# Water_motor_system.net
KiCad netlist of a schematic drawn in EAGLE
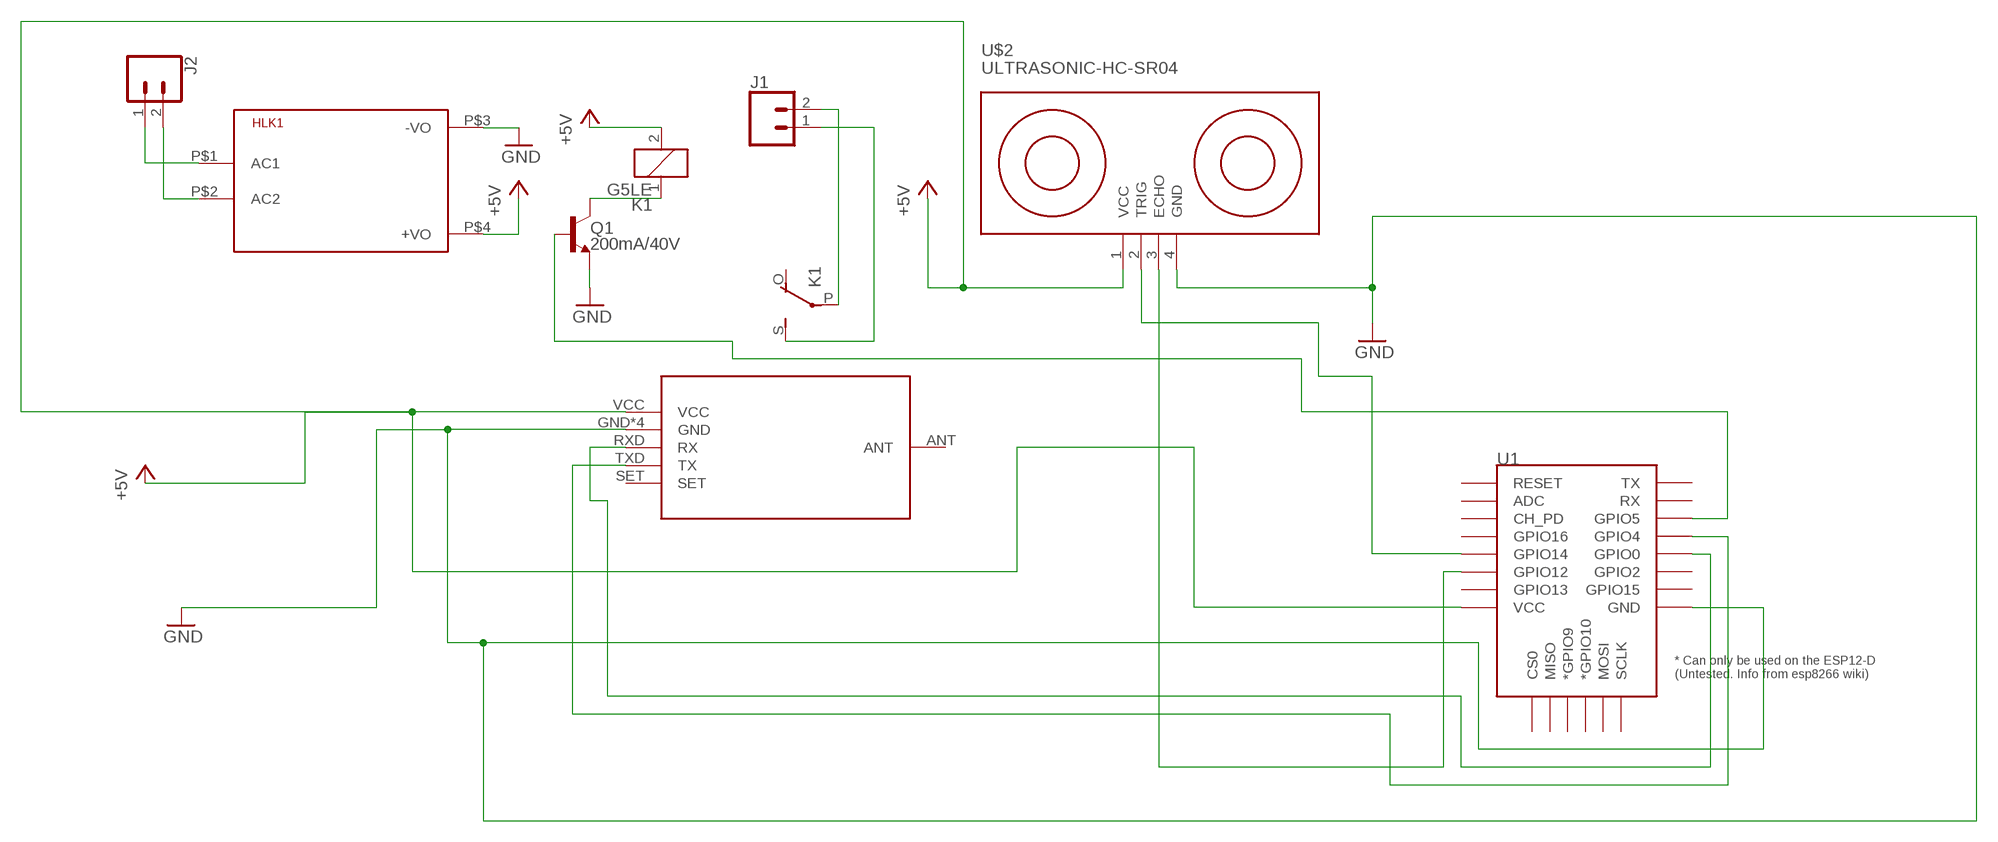
[diagram p0: schematic, sheet 1]

(export (version "E")
  (design (tool "Eeschema 10.0.6"))
  (components
    (comp (ref "HLK1")
      (value "HLK-PM013W")
      (footprint "eagle-import:HLK-PM01")
      (libsource (lib "eagle-import") (part "HLK-PM013W"))
    )
    (comp (ref "J1")
      (value "CONN_025MM")
      (footprint "eagle-import:SCREWTERMINAL-5MM-2")
      (libsource (lib "eagle-import") (part "CONN_025MM"))
    )
    (comp (ref "J2")
      (value "CONN_025MM")
      (footprint "eagle-import:SCREWTERMINAL-5MM-2")
      (libsource (lib "eagle-import") (part "CONN_025MM"))
    )
    (comp (ref "K1")
      (value "G5LE")
      (footprint "eagle-import:G5LE")
      (libsource (lib "eagle-import") (part "G5LE"))
    )
    (comp (ref "Q1")
      (value "200mA/40V")
      (footprint "eagle-import:TO-92")
      (libsource (lib "eagle-import") (part "TRANS_NPN-2N3904"))
    )
    (comp (ref "U$2")
      (value "ULTRASONIC-HC-SR04")
      (footprint "eagle-import:ULTRASONIC-HC-SR04")
      (libsource (lib "eagle-import") (part "ULTRASONIC-HC-SR04"))
    )
    (comp (ref "U$3")
      (value "HC-12_FOOTPRINT")
      (footprint "eagle-import:HC-12_FOOTPRINT")
      (libsource (lib "eagle-import") (part "HC-12_FOOTPRINT"))
    )
    (comp (ref "U1")
      (value "ESP12ESMD")
      (footprint "eagle-import:ESP12E-SMD")
      (libsource (lib "eagle-import") (part "ESP12ESMD"))
    )
  )
  (nets
    (net (code "1") (name "+5V") (class "Default")
      (node (ref "HLK1") (pin "P$4") (pinfunction "+VO_P$4") (pintype "bidirectional"))
      (node (ref "K1") (pin "2") (pinfunction "2_2") (pintype "passive"))
      (node (ref "U$2") (pin "1") (pinfunction "VCC_1") (pintype "power_in"))
      (node (ref "U$3") (pin "VCC") (pinfunction "VCC_VCC") (pintype "bidirectional"))
      (node (ref "U1") (pin "VCC") (pinfunction "VCC_VCC") (pintype "bidirectional"))
    )
    (net (code "2") (name "GND") (class "Default")
      (node (ref "HLK1") (pin "P$3") (pinfunction "-VO_P$3") (pintype "bidirectional"))
      (node (ref "Q1") (pin "1") (pinfunction "E_1") (pintype "passive"))
      (node (ref "U$2") (pin "4") (pinfunction "GND_4") (pintype "power_in"))
      (node (ref "U$3") (pin "GND") (pinfunction "GND_GND") (pintype "bidirectional"))
      (node (ref "U$3") (pin "GND1") (pinfunction "GND_GND1") (pintype "bidirectional"))
      (node (ref "U$3") (pin "GND2") (pinfunction "GND_GND2") (pintype "bidirectional"))
      (node (ref "U$3") (pin "MCHFIX") (pinfunction "GND_MCHFIX") (pintype "bidirectional"))
      (node (ref "U1") (pin "GND") (pinfunction "GND_GND") (pintype "bidirectional"))
    )
    (net (code "3") (name "Net-(HLK1-AC1)") (class "Default")
      (node (ref "HLK1") (pin "P$1") (pinfunction "AC1_P$1") (pintype "bidirectional"))
      (node (ref "J2") (pin "1") (pinfunction "1_1") (pintype "passive"))
    )
    (net (code "4") (name "Net-(HLK1-AC2)") (class "Default")
      (node (ref "HLK1") (pin "P$2") (pinfunction "AC2_P$2") (pintype "bidirectional"))
      (node (ref "J2") (pin "2") (pinfunction "2_2") (pintype "passive"))
    )
    (net (code "5") (name "Net-(J1-Pad1)") (class "Default")
      (node (ref "J1") (pin "1") (pinfunction "1_1") (pintype "passive"))
      (node (ref "K1") (pin "S") (pinfunction "S_S") (pintype "passive"))
    )
    (net (code "6") (name "Net-(J1-Pad2)") (class "Default")
      (node (ref "J1") (pin "2") (pinfunction "2_2") (pintype "passive"))
      (node (ref "K1") (pin "P") (pinfunction "P_P") (pintype "passive"))
    )
    (net (code "7") (name "Net-(Q1-B)") (class "Default")
      (node (ref "Q1") (pin "2") (pinfunction "B_2") (pintype "passive"))
      (node (ref "U1") (pin "GPIO5") (pinfunction "GPIO5_GPIO5") (pintype "bidirectional"))
    )
    (net (code "8") (name "Net-(Q1-C)") (class "Default")
      (node (ref "K1") (pin "1") (pinfunction "1_1") (pintype "passive"))
      (node (ref "Q1") (pin "3") (pinfunction "C_3") (pintype "passive"))
    )
    (net (code "9") (name "Net-(U$2-ECHO)") (class "Default")
      (node (ref "U$2") (pin "3") (pinfunction "ECHO_3") (pintype "output"))
      (node (ref "U1") (pin "GPIO12") (pinfunction "GPIO12_GPIO12") (pintype "bidirectional"))
    )
    (net (code "10") (name "Net-(U$2-TRIG)") (class "Default")
      (node (ref "U$2") (pin "2") (pinfunction "TRIG_2") (pintype "input"))
      (node (ref "U1") (pin "GPIO14") (pinfunction "GPIO14_GPIO14") (pintype "bidirectional"))
    )
    (net (code "11") (name "Net-(U$3-RX)") (class "Default")
      (node (ref "U$3") (pin "RXD") (pinfunction "RX_RXD") (pintype "bidirectional"))
      (node (ref "U1") (pin "GPIO0") (pinfunction "GPIO0_GPIO0") (pintype "bidirectional"))
    )
    (net (code "12") (name "Net-(U$3-TX)") (class "Default")
      (node (ref "U$3") (pin "TXD") (pinfunction "TX_TXD") (pintype "bidirectional"))
      (node (ref "U1") (pin "GPIO4") (pinfunction "GPIO4_GPIO4") (pintype "bidirectional"))
    )
    (net (code "13") (name "unconnected-(K1-PadO)") (class "Default")
      (node (ref "K1") (pin "O") (pinfunction "O_O") (pintype "passive"))
    )
    (net (code "14") (name "unconnected-(U$3-PadANT)") (class "Default")
      (node (ref "U$3") (pin "ANT") (pinfunction "ANT_ANT") (pintype "bidirectional"))
    )
    (net (code "15") (name "unconnected-(U$3-PadSET)") (class "Default")
      (node (ref "U$3") (pin "SET") (pinfunction "SET_SET") (pintype "bidirectional"))
    )
    (net (code "16") (name "unconnected-(U1-*GPIO9-PadGPIO9)") (class "Default")
      (node (ref "U1") (pin "GPIO9") (pinfunction "*GPIO9_GPIO9") (pintype "bidirectional"))
    )
    (net (code "17") (name "unconnected-(U1-*GPIO10-PadGPIO10)") (class "Default")
      (node (ref "U1") (pin "GPIO10") (pinfunction "*GPIO10_GPIO10") (pintype "bidirectional"))
    )
    (net (code "18") (name "unconnected-(U1-PadADC)") (class "Default")
      (node (ref "U1") (pin "ADC") (pinfunction "ADC_ADC") (pintype "bidirectional"))
    )
    (net (code "19") (name "unconnected-(U1-PadCH_PD)") (class "Default")
      (node (ref "U1") (pin "CH_PD") (pinfunction "CH_PD_CH_PD") (pintype "bidirectional"))
    )
    (net (code "20") (name "unconnected-(U1-PadCS0)") (class "Default")
      (node (ref "U1") (pin "CS0") (pinfunction "CS0_CS0") (pintype "bidirectional"))
    )
    (net (code "21") (name "unconnected-(U1-PadGPIO2)") (class "Default")
      (node (ref "U1") (pin "GPIO2") (pinfunction "GPIO2_GPIO2") (pintype "bidirectional"))
    )
    (net (code "22") (name "unconnected-(U1-PadGPIO13)") (class "Default")
      (node (ref "U1") (pin "GPIO13") (pinfunction "GPIO13_GPIO13") (pintype "bidirectional"))
    )
    (net (code "23") (name "unconnected-(U1-PadGPIO15)") (class "Default")
      (node (ref "U1") (pin "GPIO15") (pinfunction "GPIO15_GPIO15") (pintype "bidirectional"))
    )
    (net (code "24") (name "unconnected-(U1-PadGPIO16)") (class "Default")
      (node (ref "U1") (pin "GPIO16") (pinfunction "GPIO16_GPIO16") (pintype "bidirectional"))
    )
    (net (code "25") (name "unconnected-(U1-PadMISO)") (class "Default")
      (node (ref "U1") (pin "MISO") (pinfunction "MISO_MISO") (pintype "bidirectional"))
    )
    (net (code "26") (name "unconnected-(U1-PadMOSI)") (class "Default")
      (node (ref "U1") (pin "MOSI") (pinfunction "MOSI_MOSI") (pintype "bidirectional"))
    )
    (net (code "27") (name "unconnected-(U1-PadRESET)") (class "Default")
      (node (ref "U1") (pin "RESET") (pinfunction "RESET_RESET") (pintype "bidirectional"))
    )
    (net (code "28") (name "unconnected-(U1-PadSCLK)") (class "Default")
      (node (ref "U1") (pin "SCLK") (pinfunction "SCLK_SCLK") (pintype "bidirectional"))
    )
    (net (code "29") (name "unconnected-(U1-RX-PadRXD0)") (class "Default")
      (node (ref "U1") (pin "RXD0") (pinfunction "RX_RXD0") (pintype "bidirectional"))
    )
    (net (code "30") (name "unconnected-(U1-TX-PadTXD0)") (class "Default")
      (node (ref "U1") (pin "TXD0") (pinfunction "TX_TXD0") (pintype "bidirectional"))
    )
  )
)
